# Sim800.net
KiCad netlist of a schematic drawn in Altium Designer
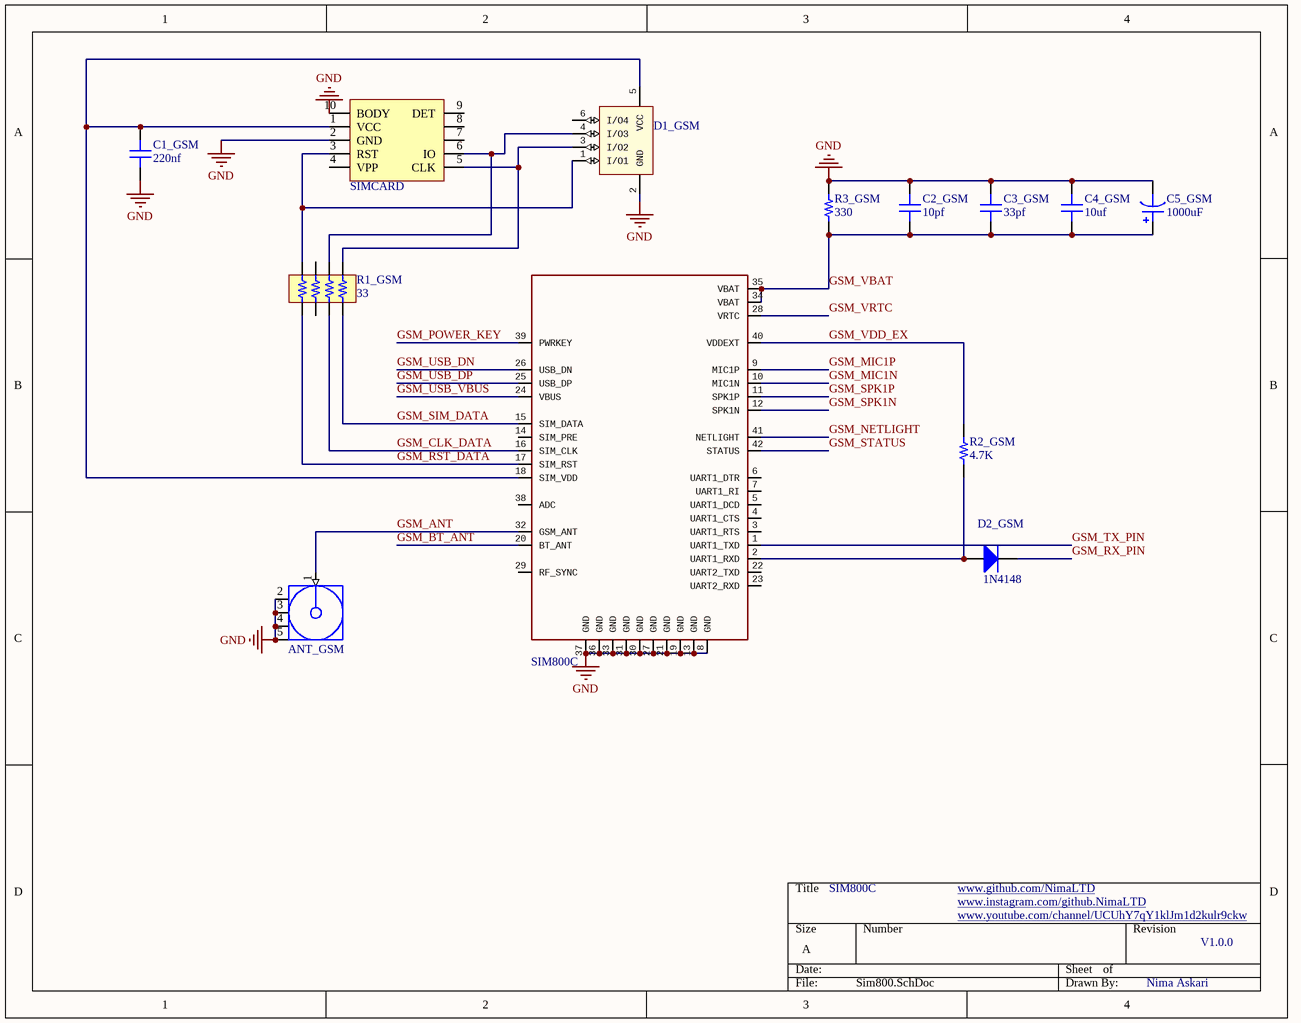
[diagram p0: Sim800.SchDoc]

(export (version "E")
  (design (tool "Eeschema 10.0.6"))
  (components
    (comp (ref "ANT_GSM") (value "SMA") (footprint "SMA_RA") (libsource (lib "CONNECTOR") (part "SMA RA")))
    (comp (ref "C1_GSM")
      (value "220nf")
      (footprint "CAP 0805")
      (description "SMT Capacitor")
      (libsource (lib "CAPACITOR") (part "Cap SMD 0805"))
    )
    (comp (ref "C2_GSM")
      (value "10pf")
      (footprint "CAP 0805")
      (description "SMT Capacitor")
      (libsource (lib "CAPACITOR") (part "Cap SMD 0805"))
    )
    (comp (ref "C3_GSM")
      (value "33pf")
      (footprint "CAP 0805")
      (description "SMT Capacitor")
      (libsource (lib "CAPACITOR") (part "Cap SMD 0805"))
    )
    (comp (ref "C4_GSM")
      (value "10uf")
      (footprint "CAP 0805")
      (description "SMT Capacitor")
      (libsource (lib "CAPACITOR") (part "Cap SMD 0805"))
    )
    (comp (ref "C5_GSM")
      (value "1000uF")
      (footprint "CAP AL SMD D8 H10")
      (description "SMT Polarised Capacitor")
      (libsource (lib "CAPACITOR") (part "Pol Cap SMD AL D8 H10"))
    )
    (comp (ref "D1_GSM")
      (value "TVS ARRAY")
      (footprint "SOT23-6")
      (description "TVS Array")
      (libsource (lib "DIODE") (part "PRTR5V0U4D"))
    )
    (comp (ref "D2_GSM")
      (value "1N4148 SMD")
      (footprint "SOD80")
      (description "Signal Diode")
      (fields (field (name "PARAMETER 1") "1N4148"))
      (libsource (lib "DIODE") (part "1N4148 SMD"))
    )
    (comp (ref "R1_GSM")
      (value "33")
      (footprint "RES PACK 0603")
      (description "SMD Resistor Pack")
      (libsource (lib "RESISTOR") (part "Res SMD Pack4 0603"))
    )
    (comp (ref "R2_GSM")
      (value "4.7K")
      (footprint "RES 0805")
      (description "SMD Resistor")
      (libsource (lib "RESISTOR") (part "Res SMD 0805"))
    )
    (comp (ref "R3_GSM")
      (value "330")
      (footprint "RES 0805")
      (description "SMD Resistor")
      (libsource (lib "RESISTOR") (part "Res SMD 0805"))
    )
    (comp (ref "SIM800C")
      (value "SIM800C")
      (footprint "M_Sim800C")
      (libsource (lib "MODULE") (part "SIM800C"))
    )
    (comp (ref "SIMCARD")
      (value "SimCard Type3")
      (footprint "SIMCARD_TYPE3")
      (libsource (lib "CONNECTOR") (part "SimCard Type3"))
    )
  )
  (nets
    (net (code "1") (name "/GSM_ANT") (class "Default")
      (node (ref "ANT_GSM") (pin "1") (pinfunction "Signal_1") (pintype "input"))
      (node (ref "SIM800C") (pin "32") (pinfunction "GSM_ANT_32") (pintype "passive"))
    )
    (net (code "2") (name "/GSM_BT_ANT") (class "Default")
      (node (ref "SIM800C") (pin "20") (pinfunction "BT_ANT_20") (pintype "passive"))
    )
    (net (code "3") (name "/GSM_CLK_DATA") (class "Default")
      (node (ref "R1_GSM") (pin "5") (pinfunction "5_5") (pintype "passive"))
      (node (ref "SIM800C") (pin "16") (pinfunction "SIM_CLK_16") (pintype "passive"))
    )
    (net (code "4") (name "/GSM_MIC1N") (class "Default")
      (node (ref "SIM800C") (pin "10") (pinfunction "MIC1N_10") (pintype "passive"))
    )
    (net (code "5") (name "/GSM_MIC1P") (class "Default")
      (node (ref "SIM800C") (pin "9") (pinfunction "MIC1P_9") (pintype "passive"))
    )
    (net (code "6") (name "/GSM_NETLIGHT") (class "Default")
      (node (ref "SIM800C") (pin "41") (pinfunction "NETLIGHT_41") (pintype "passive"))
    )
    (net (code "7") (name "/GSM_POWER_KEY") (class "Default")
      (node (ref "SIM800C") (pin "39") (pinfunction "PWRKEY_39") (pintype "passive"))
    )
    (net (code "8") (name "/GSM_RST_DATA") (class "Default")
      (node (ref "R1_GSM") (pin "1") (pinfunction "1_1") (pintype "passive"))
      (node (ref "SIM800C") (pin "17") (pinfunction "SIM_RST_17") (pintype "passive"))
    )
    (net (code "9") (name "/GSM_RX_PIN") (class "Default")
      (node (ref "D2_GSM") (pin "2") (pinfunction "K_2") (pintype "passive"))
    )
    (net (code "10") (name "/GSM_SIM_DATA") (class "Default")
      (node (ref "R1_GSM") (pin "7") (pinfunction "7_7") (pintype "passive"))
      (node (ref "SIM800C") (pin "15") (pinfunction "SIM_DATA_15") (pintype "passive"))
    )
    (net (code "11") (name "/GSM_SPK1N") (class "Default")
      (node (ref "SIM800C") (pin "12") (pinfunction "SPK1N_12") (pintype "passive"))
    )
    (net (code "12") (name "/GSM_SPK1P") (class "Default")
      (node (ref "SIM800C") (pin "11") (pinfunction "SPK1P_11") (pintype "passive"))
    )
    (net (code "13") (name "/GSM_STATUS") (class "Default")
      (node (ref "SIM800C") (pin "42") (pinfunction "STATUS_42") (pintype "passive"))
    )
    (net (code "14") (name "/GSM_TX_PIN") (class "Default")
      (node (ref "SIM800C") (pin "1") (pinfunction "UART1_TXD_1") (pintype "passive"))
    )
    (net (code "15") (name "/GSM_USB_DN") (class "Default")
      (node (ref "SIM800C") (pin "26") (pinfunction "USB_DN_26") (pintype "passive"))
    )
    (net (code "16") (name "/GSM_USB_DP") (class "Default")
      (node (ref "SIM800C") (pin "25") (pinfunction "USB_DP_25") (pintype "passive"))
    )
    (net (code "17") (name "/GSM_USB_VBUS") (class "Default")
      (node (ref "SIM800C") (pin "24") (pinfunction "VBUS_24") (pintype "passive"))
    )
    (net (code "18") (name "/GSM_VBAT") (class "Default")
      (node (ref "C2_GSM") (pin "1") (pinfunction "1_1") (pintype "passive"))
      (node (ref "C3_GSM") (pin "1") (pinfunction "1_1") (pintype "passive"))
      (node (ref "C4_GSM") (pin "1") (pinfunction "1_1") (pintype "passive"))
      (node (ref "C5_GSM") (pin "1") (pinfunction "1_1") (pintype "passive"))
      (node (ref "R3_GSM") (pin "1") (pinfunction "1_1") (pintype "passive"))
      (node (ref "SIM800C") (pin "34") (pinfunction "VBAT_34") (pintype "passive"))
      (node (ref "SIM800C") (pin "35") (pinfunction "VBAT_35") (pintype "passive"))
    )
    (net (code "19") (name "/GSM_VDD_EX") (class "Default")
      (node (ref "R2_GSM") (pin "2") (pinfunction "2_2") (pintype "passive"))
      (node (ref "SIM800C") (pin "40") (pinfunction "VDDEXT_40") (pintype "passive"))
    )
    (net (code "20") (name "/GSM_VRTC") (class "Default")
      (node (ref "SIM800C") (pin "28") (pinfunction "VRTC_28") (pintype "passive"))
    )
    (net (code "21") (name "GND") (class "Default")
      (node (ref "ANT_GSM") (pin "2") (pinfunction "GND_2") (pintype "power_in"))
      (node (ref "ANT_GSM") (pin "3") (pinfunction "GND_3") (pintype "power_in"))
      (node (ref "ANT_GSM") (pin "4") (pinfunction "GND_4") (pintype "power_in"))
      (node (ref "ANT_GSM") (pin "5") (pinfunction "GND_5") (pintype "power_in"))
      (node (ref "C1_GSM") (pin "1") (pinfunction "1_1") (pintype "passive"))
      (node (ref "C2_GSM") (pin "2") (pinfunction "2_2") (pintype "passive"))
      (node (ref "C3_GSM") (pin "2") (pinfunction "2_2") (pintype "passive"))
      (node (ref "C4_GSM") (pin "2") (pinfunction "2_2") (pintype "passive"))
      (node (ref "C5_GSM") (pin "2") (pinfunction "2_2") (pintype "passive"))
      (node (ref "D1_GSM") (pin "2") (pinfunction "GND_2") (pintype "power_in"))
      (node (ref "R3_GSM") (pin "2") (pinfunction "2_2") (pintype "passive"))
      (node (ref "SIM800C") (pin "13") (pinfunction "GND_13") (pintype "passive"))
      (node (ref "SIM800C") (pin "19") (pinfunction "GND_19") (pintype "passive"))
      (node (ref "SIM800C") (pin "21") (pinfunction "GND_21") (pintype "passive"))
      (node (ref "SIM800C") (pin "27") (pinfunction "GND_27") (pintype "passive"))
      (node (ref "SIM800C") (pin "30") (pinfunction "GND_30") (pintype "passive"))
      (node (ref "SIM800C") (pin "31") (pinfunction "GND_31") (pintype "passive"))
      (node (ref "SIM800C") (pin "33") (pinfunction "GND_33") (pintype "passive"))
      (node (ref "SIM800C") (pin "36") (pinfunction "GND_36") (pintype "passive"))
      (node (ref "SIM800C") (pin "37") (pinfunction "GND_37") (pintype "passive"))
      (node (ref "SIM800C") (pin "8") (pinfunction "GND_8") (pintype "passive"))
      (node (ref "SIMCARD") (pin "10") (pinfunction "BODY_10") (pintype "passive"))
      (node (ref "SIMCARD") (pin "2") (pinfunction "GND_2") (pintype "passive"))
    )
    (net (code "22") (name "Net-(D1_GSM-I{slash}O1)") (class "Default")
      (node (ref "D1_GSM") (pin "1") (pinfunction "I/O1_1") (pintype "bidirectional"))
      (node (ref "R1_GSM") (pin "2") (pinfunction "2_2") (pintype "passive"))
      (node (ref "SIMCARD") (pin "3") (pinfunction "RST_3") (pintype "passive"))
    )
    (net (code "23") (name "Net-(D1_GSM-I{slash}O2)") (class "Default")
      (node (ref "D1_GSM") (pin "3") (pinfunction "I/O2_3") (pintype "bidirectional"))
      (node (ref "R1_GSM") (pin "8") (pinfunction "8_8") (pintype "passive"))
      (node (ref "SIMCARD") (pin "5") (pinfunction "CLK_5") (pintype "passive"))
    )
    (net (code "24") (name "Net-(D1_GSM-I{slash}O3)") (class "Default")
      (node (ref "D1_GSM") (pin "4") (pinfunction "I/O3_4") (pintype "bidirectional"))
      (node (ref "R1_GSM") (pin "6") (pinfunction "6_6") (pintype "passive"))
      (node (ref "SIMCARD") (pin "6") (pinfunction "IO_6") (pintype "passive"))
    )
    (net (code "25") (name "Net-(D1_GSM-VCC)") (class "Default")
      (node (ref "C1_GSM") (pin "2") (pinfunction "2_2") (pintype "passive"))
      (node (ref "D1_GSM") (pin "5") (pinfunction "VCC_5") (pintype "power_in"))
      (node (ref "SIM800C") (pin "18") (pinfunction "SIM_VDD_18") (pintype "passive"))
      (node (ref "SIMCARD") (pin "1") (pinfunction "VCC_1") (pintype "passive"))
    )
    (net (code "26") (name "Net-(D2_GSM-A)") (class "Default")
      (node (ref "D2_GSM") (pin "1") (pinfunction "A_1") (pintype "passive"))
      (node (ref "R2_GSM") (pin "1") (pinfunction "1_1") (pintype "passive"))
      (node (ref "SIM800C") (pin "2") (pinfunction "UART1_RXD_2") (pintype "passive"))
    )
    (net (code "27") (name "unconnected-(D1_GSM-I{slash}O4-Pad6)") (class "Default")
      (node (ref "D1_GSM") (pin "6") (pinfunction "I/O4_6") (pintype "bidirectional"))
    )
    (net (code "28") (name "unconnected-(R1_GSM-Pad3)") (class "Default")
      (node (ref "R1_GSM") (pin "3") (pinfunction "3_3") (pintype "passive"))
    )
    (net (code "29") (name "unconnected-(R1_GSM-Pad4)") (class "Default")
      (node (ref "R1_GSM") (pin "4") (pinfunction "4_4") (pintype "passive"))
    )
    (net (code "30") (name "unconnected-(SIM800C-ADC-Pad38)") (class "Default")
      (node (ref "SIM800C") (pin "38") (pinfunction "ADC_38") (pintype "passive"))
    )
    (net (code "31") (name "unconnected-(SIM800C-RF_SYNC-Pad29)") (class "Default")
      (node (ref "SIM800C") (pin "29") (pinfunction "RF_SYNC_29") (pintype "passive"))
    )
    (net (code "32") (name "unconnected-(SIM800C-SIM_PRE-Pad14)") (class "Default")
      (node (ref "SIM800C") (pin "14") (pinfunction "SIM_PRE_14") (pintype "passive"))
    )
    (net (code "33") (name "unconnected-(SIM800C-UART1_CTS-Pad4)") (class "Default")
      (node (ref "SIM800C") (pin "4") (pinfunction "UART1_CTS_4") (pintype "passive"))
    )
    (net (code "34") (name "unconnected-(SIM800C-UART1_DCD-Pad5)") (class "Default")
      (node (ref "SIM800C") (pin "5") (pinfunction "UART1_DCD_5") (pintype "passive"))
    )
    (net (code "35") (name "unconnected-(SIM800C-UART1_DTR-Pad6)") (class "Default")
      (node (ref "SIM800C") (pin "6") (pinfunction "UART1_DTR_6") (pintype "passive"))
    )
    (net (code "36") (name "unconnected-(SIM800C-UART1_RI-Pad7)") (class "Default")
      (node (ref "SIM800C") (pin "7") (pinfunction "UART1_RI_7") (pintype "passive"))
    )
    (net (code "37") (name "unconnected-(SIM800C-UART1_RTS-Pad3)") (class "Default")
      (node (ref "SIM800C") (pin "3") (pinfunction "UART1_RTS_3") (pintype "passive"))
    )
    (net (code "38") (name "unconnected-(SIM800C-UART2_RXD-Pad23)") (class "Default")
      (node (ref "SIM800C") (pin "23") (pinfunction "UART2_RXD_23") (pintype "passive"))
    )
    (net (code "39") (name "unconnected-(SIM800C-UART2_TXD-Pad22)") (class "Default")
      (node (ref "SIM800C") (pin "22") (pinfunction "UART2_TXD_22") (pintype "passive"))
    )
    (net (code "40") (name "unconnected-(SIMCARD-DET-Pad9)") (class "Default")
      (node (ref "SIMCARD") (pin "9") (pinfunction "DET_9") (pintype "passive"))
    )
    (net (code "41") (name "unconnected-(SIMCARD-Pad7)") (class "Default")
      (node (ref "SIMCARD") (pin "7") (pintype "passive"))
    )
    (net (code "42") (name "unconnected-(SIMCARD-Pad8)") (class "Default")
      (node (ref "SIMCARD") (pin "8") (pintype "passive"))
    )
    (net (code "43") (name "unconnected-(SIMCARD-VPP-Pad4)") (class "Default")
      (node (ref "SIMCARD") (pin "4") (pinfunction "VPP_4") (pintype "passive"))
    )
  )
)
